# nRF51822.net
KiCad netlist of a schematic drawn in EAGLE
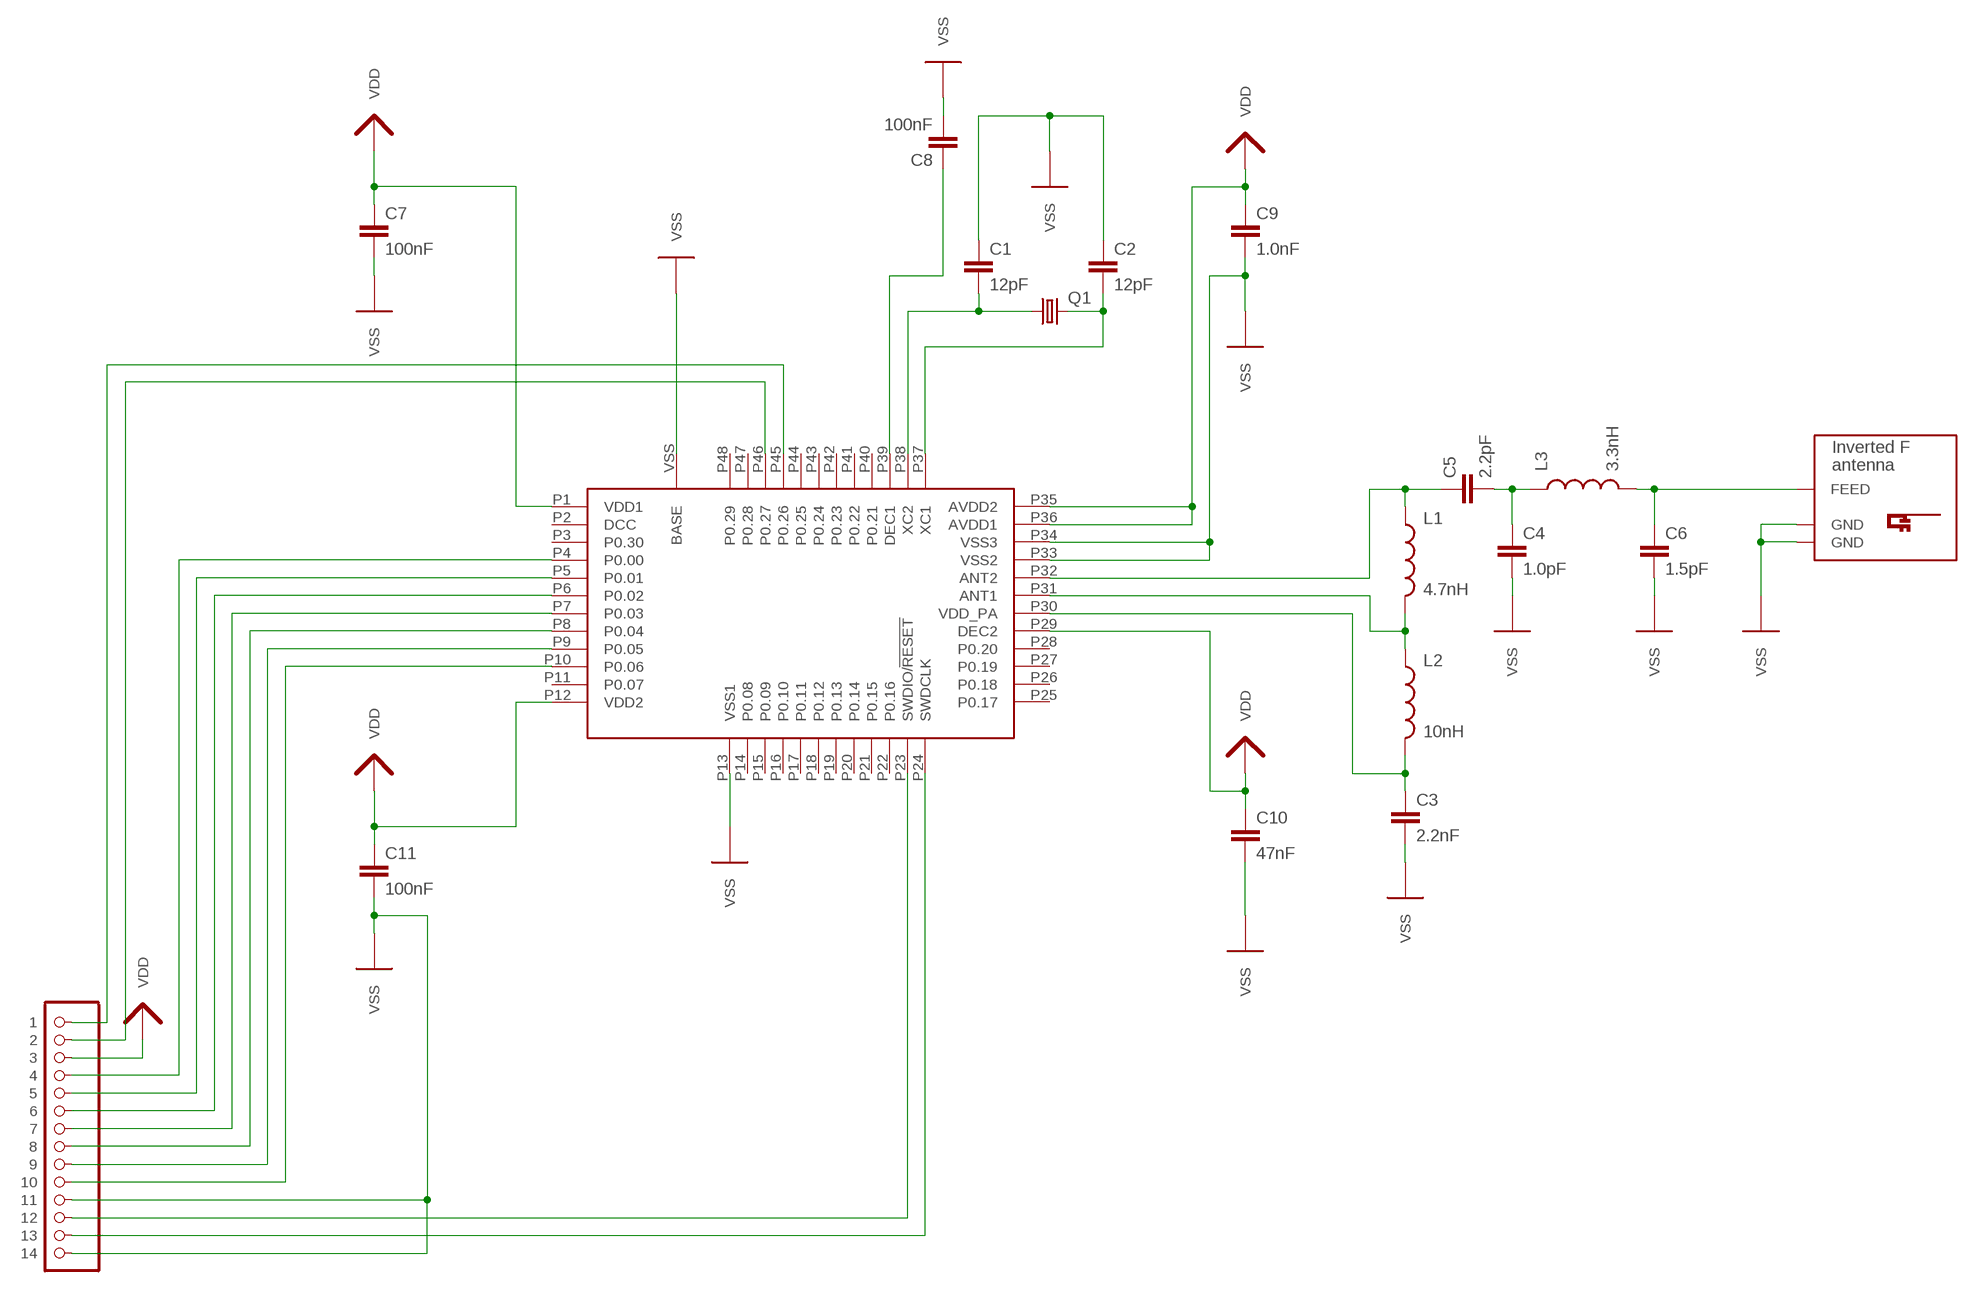
[diagram p0: schematic, sheet 1]

(export (version "E")
  (design (tool "Eeschema 10.0.6"))
  (components
    (comp (ref "C1")
      (value "12pF")
      (footprint "eagle-import:0805")
      (libsource (lib "eagle-import") (part "CAP0805"))
    )
    (comp (ref "C2")
      (value "12pF")
      (footprint "eagle-import:0805")
      (libsource (lib "eagle-import") (part "CAP0805"))
    )
    (comp (ref "C3")
      (value "2.2nF")
      (footprint "eagle-import:0805")
      (libsource (lib "eagle-import") (part "CAP0805"))
    )
    (comp (ref "C4")
      (value "1.0pF")
      (footprint "eagle-import:0805")
      (libsource (lib "eagle-import") (part "CAP0805"))
    )
    (comp (ref "C5")
      (value "2.2pF")
      (footprint "eagle-import:0805")
      (libsource (lib "eagle-import") (part "CAP0805"))
    )
    (comp (ref "C6")
      (value "1.5pF")
      (footprint "eagle-import:0805")
      (libsource (lib "eagle-import") (part "CAP0805"))
    )
    (comp (ref "C7")
      (value "100nF")
      (footprint "eagle-import:0805")
      (libsource (lib "eagle-import") (part "CAP0805"))
    )
    (comp (ref "C8")
      (value "100nF")
      (footprint "eagle-import:0805")
      (libsource (lib "eagle-import") (part "CAP0805"))
    )
    (comp (ref "C9")
      (value "1.0nF")
      (footprint "eagle-import:0805")
      (libsource (lib "eagle-import") (part "CAP0805"))
    )
    (comp (ref "C10")
      (value "47nF")
      (footprint "eagle-import:0805")
      (libsource (lib "eagle-import") (part "CAP0805"))
    )
    (comp (ref "C11")
      (value "100nF")
      (footprint "eagle-import:0805")
      (libsource (lib "eagle-import") (part "CAP0805"))
    )
    (comp (ref "L1")
      (value "4.7nH")
      (footprint "eagle-import:0805")
      (libsource (lib "eagle-import") (part "INDUCTOR0805"))
    )
    (comp (ref "L2")
      (value "10nH")
      (footprint "eagle-import:0805")
      (libsource (lib "eagle-import") (part "INDUCTOR0805"))
    )
    (comp (ref "L3")
      (value "3.3nH")
      (footprint "eagle-import:0805")
      (libsource (lib "eagle-import") (part "INDUCTOR0805"))
    )
    (comp (ref "Q1")
      (value "FC-12M")
      (footprint "eagle-import:FC-12M")
      (libsource (lib "eagle-import") (part "FC-12M"))
    )
    (comp (ref "U$2")
      (value "INVERTED_F_ANTENNA+2")
      (footprint "eagle-import:DN007+2")
      (libsource (lib "eagle-import") (part "INVERTED_F_ANTENNA+2"))
    )
    (comp (ref "U$3")
      (value "PINHD-1X14")
      (footprint "eagle-import:1X14")
      (libsource (lib "eagle-import") (part "PINHD-1X14"))
    )
    (comp (ref "U1")
      (value "nRF51822")
      (footprint "eagle-import:QFN48")
      (libsource (lib "eagle-import") (part "NRF51822"))
    )
  )
  (nets
    (net (code "1") (name "Net-(C4-Pad1)") (class "Default")
      (node (ref "C4") (pin "1") (pinfunction "1_1") (pintype "passive"))
      (node (ref "C5") (pin "2") (pinfunction "2_2") (pintype "passive"))
      (node (ref "L3") (pin "1") (pinfunction "1_1") (pintype "passive"))
    )
    (net (code "2") (name "Net-(C6-Pad1)") (class "Default")
      (node (ref "C6") (pin "1") (pinfunction "1_1") (pintype "passive"))
      (node (ref "L3") (pin "2") (pinfunction "2_2") (pintype "passive"))
      (node (ref "U$2") (pin "FEED") (pinfunction "FEED_FEED") (pintype "bidirectional"))
    )
    (net (code "3") (name "Net-(U1-ANT1)") (class "Default")
      (node (ref "L1") (pin "2") (pinfunction "2_2") (pintype "passive"))
      (node (ref "L2") (pin "1") (pinfunction "1_1") (pintype "passive"))
      (node (ref "U1") (pin "P31") (pinfunction "ANT1_P31") (pintype "bidirectional"))
    )
    (net (code "4") (name "Net-(U1-ANT2)") (class "Default")
      (node (ref "C5") (pin "1") (pinfunction "1_1") (pintype "passive"))
      (node (ref "L1") (pin "1") (pinfunction "1_1") (pintype "passive"))
      (node (ref "U1") (pin "P32") (pinfunction "ANT2_P32") (pintype "bidirectional"))
    )
    (net (code "5") (name "Net-(U1-DEC1)") (class "Default")
      (node (ref "C8") (pin "1") (pinfunction "1_1") (pintype "passive"))
      (node (ref "U1") (pin "P39") (pinfunction "DEC1_P39") (pintype "bidirectional"))
    )
    (net (code "6") (name "Net-(U1-P0.00)") (class "Default")
      (node (ref "U$3") (pin "4") (pinfunction "4_4") (pintype "passive"))
      (node (ref "U1") (pin "P4") (pinfunction "P0.00_P4") (pintype "bidirectional"))
    )
    (net (code "7") (name "Net-(U1-P0.01)") (class "Default")
      (node (ref "U$3") (pin "5") (pinfunction "5_5") (pintype "passive"))
      (node (ref "U1") (pin "P5") (pinfunction "P0.01_P5") (pintype "bidirectional"))
    )
    (net (code "8") (name "Net-(U1-P0.02)") (class "Default")
      (node (ref "U$3") (pin "6") (pinfunction "6_6") (pintype "passive"))
      (node (ref "U1") (pin "P6") (pinfunction "P0.02_P6") (pintype "bidirectional"))
    )
    (net (code "9") (name "Net-(U1-P0.03)") (class "Default")
      (node (ref "U$3") (pin "7") (pinfunction "7_7") (pintype "passive"))
      (node (ref "U1") (pin "P7") (pinfunction "P0.03_P7") (pintype "bidirectional"))
    )
    (net (code "10") (name "Net-(U1-P0.04)") (class "Default")
      (node (ref "U$3") (pin "8") (pinfunction "8_8") (pintype "passive"))
      (node (ref "U1") (pin "P8") (pinfunction "P0.04_P8") (pintype "bidirectional"))
    )
    (net (code "11") (name "Net-(U1-P0.05)") (class "Default")
      (node (ref "U$3") (pin "9") (pinfunction "9_9") (pintype "passive"))
      (node (ref "U1") (pin "P9") (pinfunction "P0.05_P9") (pintype "bidirectional"))
    )
    (net (code "12") (name "Net-(U1-P0.06)") (class "Default")
      (node (ref "U$3") (pin "10") (pinfunction "10_10") (pintype "passive"))
      (node (ref "U1") (pin "P10") (pinfunction "P0.06_P10") (pintype "bidirectional"))
    )
    (net (code "13") (name "Net-(U1-P0.26)") (class "Default")
      (node (ref "U$3") (pin "1") (pinfunction "1_1") (pintype "passive"))
      (node (ref "U1") (pin "P45") (pinfunction "P0.26_P45") (pintype "bidirectional"))
    )
    (net (code "14") (name "Net-(U1-P0.27)") (class "Default")
      (node (ref "U$3") (pin "2") (pinfunction "2_2") (pintype "passive"))
      (node (ref "U1") (pin "P46") (pinfunction "P0.27_P46") (pintype "bidirectional"))
    )
    (net (code "15") (name "Net-(U1-SWDCLK)") (class "Default")
      (node (ref "U$3") (pin "13") (pinfunction "13_13") (pintype "passive"))
      (node (ref "U1") (pin "P24") (pinfunction "SWDCLK_P24") (pintype "bidirectional"))
    )
    (net (code "16") (name "Net-(U1-SWDIO{slash}~{RESET})") (class "Default")
      (node (ref "U$3") (pin "12") (pinfunction "12_12") (pintype "passive"))
      (node (ref "U1") (pin "P23") (pinfunction "SWDIO/~{RESET}_P23") (pintype "bidirectional"))
    )
    (net (code "17") (name "Net-(U1-VDD_PA)") (class "Default")
      (node (ref "C3") (pin "1") (pinfunction "1_1") (pintype "passive"))
      (node (ref "L2") (pin "2") (pinfunction "2_2") (pintype "passive"))
      (node (ref "U1") (pin "P30") (pinfunction "VDD_PA_P30") (pintype "bidirectional"))
    )
    (net (code "18") (name "Net-(U1-XC1)") (class "Default")
      (node (ref "C2") (pin "2") (pinfunction "2_2") (pintype "passive"))
      (node (ref "Q1") (pin "2") (pinfunction "2_2") (pintype "passive"))
      (node (ref "U1") (pin "P37") (pinfunction "XC1_P37") (pintype "bidirectional"))
    )
    (net (code "19") (name "Net-(U1-XC2)") (class "Default")
      (node (ref "C1") (pin "2") (pinfunction "2_2") (pintype "passive"))
      (node (ref "Q1") (pin "1") (pinfunction "1_1") (pintype "passive"))
      (node (ref "U1") (pin "P38") (pinfunction "XC2_P38") (pintype "bidirectional"))
    )
    (net (code "20") (name "VDD") (class "Default")
      (node (ref "C10") (pin "1") (pinfunction "1_1") (pintype "passive"))
      (node (ref "C11") (pin "1") (pinfunction "1_1") (pintype "passive"))
      (node (ref "C7") (pin "1") (pinfunction "1_1") (pintype "passive"))
      (node (ref "C9") (pin "1") (pinfunction "1_1") (pintype "passive"))
      (node (ref "U$3") (pin "3") (pinfunction "3_3") (pintype "passive"))
      (node (ref "U1") (pin "P1") (pinfunction "VDD1_P1") (pintype "bidirectional"))
      (node (ref "U1") (pin "P12") (pinfunction "VDD2_P12") (pintype "bidirectional"))
      (node (ref "U1") (pin "P29") (pinfunction "DEC2_P29") (pintype "bidirectional"))
      (node (ref "U1") (pin "P35") (pinfunction "AVDD2_P35") (pintype "bidirectional"))
      (node (ref "U1") (pin "P36") (pinfunction "AVDD1_P36") (pintype "bidirectional"))
    )
    (net (code "21") (name "VSS") (class "Default")
      (node (ref "C1") (pin "1") (pinfunction "1_1") (pintype "passive"))
      (node (ref "C10") (pin "2") (pinfunction "2_2") (pintype "passive"))
      (node (ref "C11") (pin "2") (pinfunction "2_2") (pintype "passive"))
      (node (ref "C2") (pin "1") (pinfunction "1_1") (pintype "passive"))
      (node (ref "C3") (pin "2") (pinfunction "2_2") (pintype "passive"))
      (node (ref "C4") (pin "2") (pinfunction "2_2") (pintype "passive"))
      (node (ref "C6") (pin "2") (pinfunction "2_2") (pintype "passive"))
      (node (ref "C7") (pin "2") (pinfunction "2_2") (pintype "passive"))
      (node (ref "C8") (pin "2") (pinfunction "2_2") (pintype "passive"))
      (node (ref "C9") (pin "2") (pinfunction "2_2") (pintype "passive"))
      (node (ref "U$2") (pin "GND") (pinfunction "GND_GND") (pintype "bidirectional"))
      (node (ref "U$2") (pin "GND@1") (pinfunction "GND_GND@1") (pintype "bidirectional"))
      (node (ref "U$3") (pin "11") (pinfunction "11_11") (pintype "passive"))
      (node (ref "U$3") (pin "14") (pinfunction "14_14") (pintype "passive"))
      (node (ref "U1") (pin "P13") (pinfunction "VSS1_P13") (pintype "bidirectional"))
      (node (ref "U1") (pin "P33") (pinfunction "VSS2_P33") (pintype "bidirectional"))
      (node (ref "U1") (pin "P34") (pinfunction "VSS3_P34") (pintype "bidirectional"))
      (node (ref "U1") (pin "VSS") (pinfunction "BASE_VSS") (pintype "bidirectional"))
    )
    (net (code "22") (name "unconnected-(U1-DCC-PadP2)") (class "Default")
      (node (ref "U1") (pin "P2") (pinfunction "DCC_P2") (pintype "bidirectional"))
    )
    (net (code "23") (name "unconnected-(U1-P0.07-PadP11)") (class "Default")
      (node (ref "U1") (pin "P11") (pinfunction "P0.07_P11") (pintype "bidirectional"))
    )
    (net (code "24") (name "unconnected-(U1-P0.08-PadP14)") (class "Default")
      (node (ref "U1") (pin "P14") (pinfunction "P0.08_P14") (pintype "bidirectional"))
    )
    (net (code "25") (name "unconnected-(U1-P0.09-PadP15)") (class "Default")
      (node (ref "U1") (pin "P15") (pinfunction "P0.09_P15") (pintype "bidirectional"))
    )
    (net (code "26") (name "unconnected-(U1-P0.10-PadP16)") (class "Default")
      (node (ref "U1") (pin "P16") (pinfunction "P0.10_P16") (pintype "bidirectional"))
    )
    (net (code "27") (name "unconnected-(U1-P0.11-PadP17)") (class "Default")
      (node (ref "U1") (pin "P17") (pinfunction "P0.11_P17") (pintype "bidirectional"))
    )
    (net (code "28") (name "unconnected-(U1-P0.12-PadP18)") (class "Default")
      (node (ref "U1") (pin "P18") (pinfunction "P0.12_P18") (pintype "bidirectional"))
    )
    (net (code "29") (name "unconnected-(U1-P0.13-PadP19)") (class "Default")
      (node (ref "U1") (pin "P19") (pinfunction "P0.13_P19") (pintype "bidirectional"))
    )
    (net (code "30") (name "unconnected-(U1-P0.14-PadP20)") (class "Default")
      (node (ref "U1") (pin "P20") (pinfunction "P0.14_P20") (pintype "bidirectional"))
    )
    (net (code "31") (name "unconnected-(U1-P0.15-PadP21)") (class "Default")
      (node (ref "U1") (pin "P21") (pinfunction "P0.15_P21") (pintype "bidirectional"))
    )
    (net (code "32") (name "unconnected-(U1-P0.16-PadP22)") (class "Default")
      (node (ref "U1") (pin "P22") (pinfunction "P0.16_P22") (pintype "bidirectional"))
    )
    (net (code "33") (name "unconnected-(U1-P0.17-PadP25)") (class "Default")
      (node (ref "U1") (pin "P25") (pinfunction "P0.17_P25") (pintype "bidirectional"))
    )
    (net (code "34") (name "unconnected-(U1-P0.18-PadP26)") (class "Default")
      (node (ref "U1") (pin "P26") (pinfunction "P0.18_P26") (pintype "bidirectional"))
    )
    (net (code "35") (name "unconnected-(U1-P0.19-PadP27)") (class "Default")
      (node (ref "U1") (pin "P27") (pinfunction "P0.19_P27") (pintype "bidirectional"))
    )
    (net (code "36") (name "unconnected-(U1-P0.20-PadP28)") (class "Default")
      (node (ref "U1") (pin "P28") (pinfunction "P0.20_P28") (pintype "bidirectional"))
    )
    (net (code "37") (name "unconnected-(U1-P0.21-PadP40)") (class "Default")
      (node (ref "U1") (pin "P40") (pinfunction "P0.21_P40") (pintype "bidirectional"))
    )
    (net (code "38") (name "unconnected-(U1-P0.22-PadP41)") (class "Default")
      (node (ref "U1") (pin "P41") (pinfunction "P0.22_P41") (pintype "bidirectional"))
    )
    (net (code "39") (name "unconnected-(U1-P0.23-PadP42)") (class "Default")
      (node (ref "U1") (pin "P42") (pinfunction "P0.23_P42") (pintype "bidirectional"))
    )
    (net (code "40") (name "unconnected-(U1-P0.24-PadP43)") (class "Default")
      (node (ref "U1") (pin "P43") (pinfunction "P0.24_P43") (pintype "bidirectional"))
    )
    (net (code "41") (name "unconnected-(U1-P0.25-PadP44)") (class "Default")
      (node (ref "U1") (pin "P44") (pinfunction "P0.25_P44") (pintype "bidirectional"))
    )
    (net (code "42") (name "unconnected-(U1-P0.28-PadP47)") (class "Default")
      (node (ref "U1") (pin "P47") (pinfunction "P0.28_P47") (pintype "bidirectional"))
    )
    (net (code "43") (name "unconnected-(U1-P0.29-PadP48)") (class "Default")
      (node (ref "U1") (pin "P48") (pinfunction "P0.29_P48") (pintype "bidirectional"))
    )
    (net (code "44") (name "unconnected-(U1-P0.30-PadP3)") (class "Default")
      (node (ref "U1") (pin "P3") (pinfunction "P0.30_P3") (pintype "bidirectional"))
    )
  )
)
